# RX-FM-Radio-Simple-Dip2.net
KiCad netlist of a schematic drawn in EAGLE
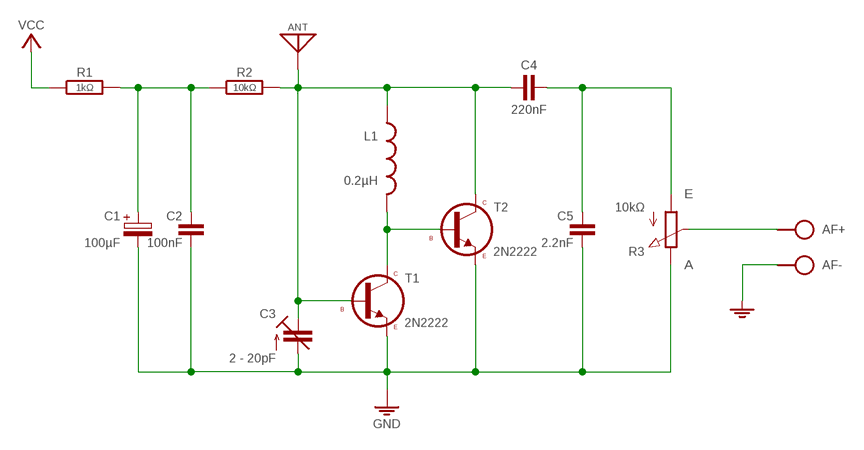
[diagram p0: schematic, sheet 1]

(export (version "E")
  (design (tool "Eeschema 10.0.6"))
  (components
    (comp (ref "AF")
      (value "SPAD+-+-")
      (footprint "eagle-import:SPAD+-")
      (libsource (lib "eagle-import") (part "SPAD+-+-"))
    )
    (comp (ref "ANT")
      (value "ANT")
      (footprint "eagle-import:SPAD")
      (libsource (lib "eagle-import") (part "ANT"))
    )
    (comp (ref "BAT")
      (value "VCC_GNDL")
      (footprint "eagle-import:SPAD-+")
      (libsource (lib "eagle-import") (part "VCC_GNDL"))
    )
    (comp (ref "C1")
      (value "100µF")
      (footprint "eagle-import:E2,5-5_V")
      (libsource (lib "eagle-import") (part "CPOLE2,5-5/V"))
    )
    (comp (ref "C2")
      (value "100nF")
      (footprint "eagle-import:C050-020X036_V")
      (libsource (lib "eagle-import") (part "C050-020X036/V"))
    )
    (comp (ref "C3")
      (value "2 - 20pF")
      (footprint "eagle-import:TRIM-2222-808")
      (libsource (lib "eagle-import") (part "C-TR-PH201272222-808-2PIND"))
    )
    (comp (ref "C4")
      (value "220nF")
      (footprint "eagle-import:C050-020X044")
      (libsource (lib "eagle-import") (part "C-H050-020X044"))
    )
    (comp (ref "C5")
      (value "2.2nF")
      (footprint "eagle-import:C050-020X036_V")
      (libsource (lib "eagle-import") (part "C050-020X036/V"))
    )
    (comp (ref "L1")
      (value "0.2µH")
      (footprint "eagle-import:L-10_10Y")
      (libsource (lib "eagle-import") (part "L10/10Y"))
    )
    (comp (ref "R1")
      (value "1kΩ")
      (footprint "eagle-import:0204_10")
      (libsource (lib "eagle-import") (part "R-H0204/10"))
    )
    (comp (ref "R2")
      (value "10kΩ")
      (footprint "eagle-import:0204_10")
      (libsource (lib "eagle-import") (part "R-H0204/10"))
    )
    (comp (ref "R3")
      (value "10kΩ")
      (footprint "eagle-import:CONN-3P")
      (libsource (lib "eagle-import") (part "POT-3P"))
    )
    (comp (ref "T1")
      (value "2N2222")
      (footprint "eagle-import:TO92")
      (libsource (lib "eagle-import") (part "2N2222"))
    )
    (comp (ref "T2")
      (value "2N2222")
      (footprint "eagle-import:TO92")
      (libsource (lib "eagle-import") (part "2N2222"))
    )
  )
  (nets
    (net (code "1") (name "GND") (class "Default")
      (node (ref "AF") (pin "1") (pinfunction "P$1_1") (pintype "passive"))
      (node (ref "BAT") (pin "1") (pinfunction "GND_1") (pintype "power_in"))
      (node (ref "C1") (pin "-") (pinfunction "-_-") (pintype "passive"))
      (node (ref "C2") (pin "2") (pinfunction "2_2") (pintype "passive"))
      (node (ref "C3") (pin "2") (pinfunction "A_2") (pintype "passive"))
      (node (ref "C5") (pin "2") (pinfunction "2_2") (pintype "passive"))
      (node (ref "R3") (pin "3") (pinfunction "E_3") (pintype "passive"))
      (node (ref "T1") (pin "1") (pinfunction "E_1") (pintype "passive"))
      (node (ref "T2") (pin "1") (pinfunction "E_1") (pintype "passive"))
    )
    (net (code "2") (name "Net-(AFA-P$1)") (class "Default")
      (node (ref "AF") (pin "2") (pinfunction "P$1_2") (pintype "passive"))
      (node (ref "R3") (pin "2") (pinfunction "S_2") (pintype "passive"))
    )
    (net (code "3") (name "Net-(BATA-VCC)") (class "Default")
      (node (ref "BAT") (pin "2") (pinfunction "VCC_2") (pintype "power_in"))
      (node (ref "R1") (pin "1") (pinfunction "1_1") (pintype "passive"))
    )
    (net (code "4") (name "Net-(C1-Pad+)") (class "Default")
      (node (ref "C1") (pin "+") (pinfunction "+_+") (pintype "passive"))
      (node (ref "C2") (pin "1") (pinfunction "1_1") (pintype "passive"))
      (node (ref "R1") (pin "2") (pinfunction "2_2") (pintype "passive"))
      (node (ref "R2") (pin "1") (pinfunction "1_1") (pintype "passive"))
    )
    (net (code "5") (name "Net-(C3-E)") (class "Default")
      (node (ref "ANT") (pin "1") (pinfunction "1_1") (pintype "output"))
      (node (ref "C3") (pin "3") (pinfunction "E_3") (pintype "passive"))
      (node (ref "C4") (pin "1") (pinfunction "1_1") (pintype "passive"))
      (node (ref "L1") (pin "P$1") (pinfunction "1_P$1") (pintype "passive"))
      (node (ref "R2") (pin "2") (pinfunction "2_2") (pintype "passive"))
      (node (ref "T1") (pin "2") (pinfunction "B_2") (pintype "passive"))
      (node (ref "T2") (pin "3") (pinfunction "C_3") (pintype "passive"))
    )
    (net (code "6") (name "Net-(L1-2)") (class "Default")
      (node (ref "L1") (pin "P$2") (pinfunction "2_P$2") (pintype "passive"))
      (node (ref "T1") (pin "3") (pinfunction "C_3") (pintype "passive"))
      (node (ref "T2") (pin "2") (pinfunction "B_2") (pintype "passive"))
    )
    (net (code "7") (name "Net-(R3-A)") (class "Default")
      (node (ref "C4") (pin "2") (pinfunction "2_2") (pintype "passive"))
      (node (ref "C5") (pin "1") (pinfunction "1_1") (pintype "passive"))
      (node (ref "R3") (pin "1") (pinfunction "A_1") (pintype "passive"))
    )
  )
)
